# V1_6.net
KiCad netlist of a schematic drawn in Altium Designer
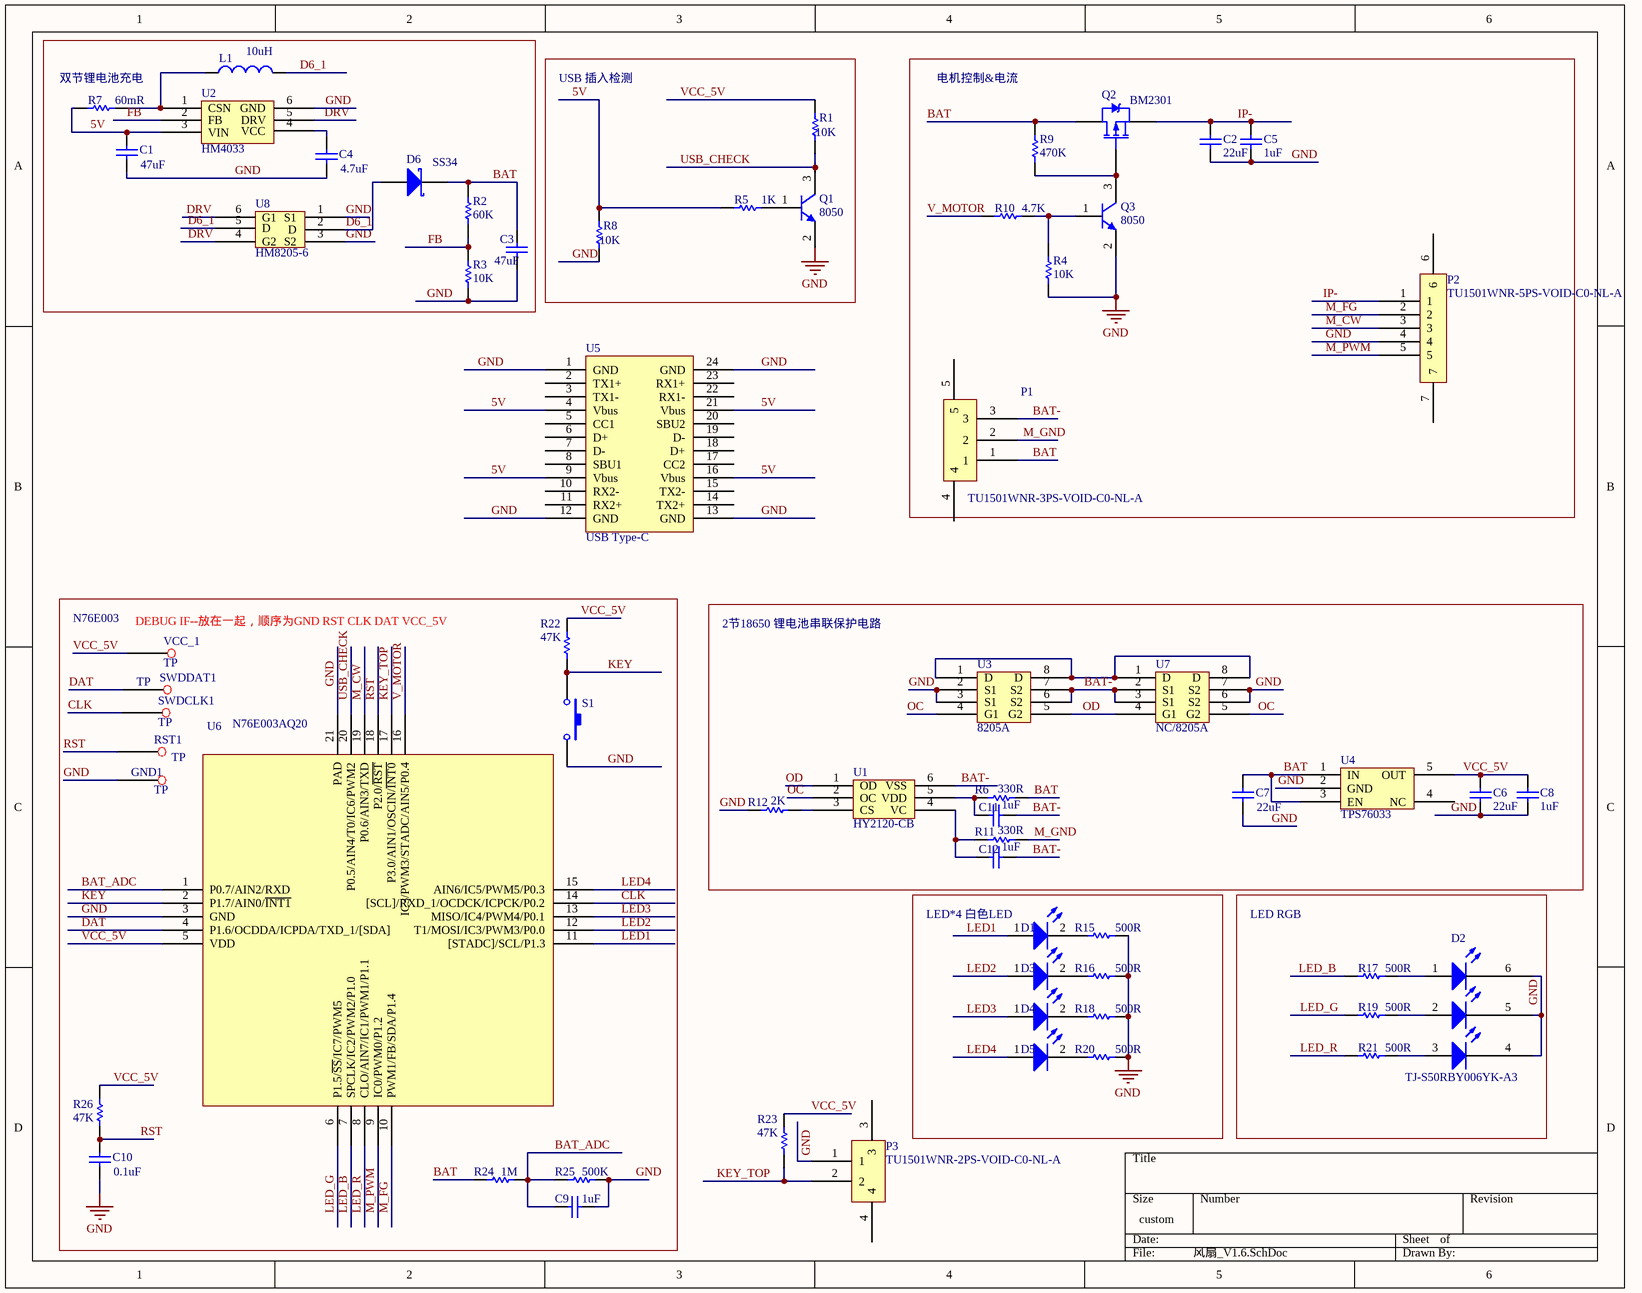
[diagram p0: 风扇_V1.6.SchDoc]

(export (version "E")
  (design (tool "Eeschema 10.0.6"))
  (components
    (comp (ref "C1")
      (value "47uF")
      (footprint "C-0603")
      (description "Capacitor")
      (fields (field (name "PUBLISHER") "Altium Limited"))
      (libsource (lib "Miscellaneous Devices") (part "Cap"))
    )
    (comp (ref "C2")
      (value "22uF")
      (footprint "C-0603")
      (description "Capacitor")
      (fields (field (name "PUBLISHER") "Altium Limited"))
      (libsource (lib "Miscellaneous Devices") (part "Cap"))
    )
    (comp (ref "C3")
      (value "47uF")
      (footprint "C-0603")
      (description "Capacitor")
      (fields (field (name "PUBLISHER") "Altium Limited"))
      (libsource (lib "Miscellaneous Devices") (part "Cap"))
    )
    (comp (ref "C4")
      (value "4.7uF")
      (footprint "C-0402")
      (description "Capacitor")
      (fields (field (name "PUBLISHER") "Altium Limited"))
      (libsource (lib "Miscellaneous Devices") (part "Cap"))
    )
    (comp (ref "C5")
      (value "1uF")
      (footprint "C-0402")
      (description "Capacitor")
      (fields (field (name "PUBLISHER") "Altium Limited"))
      (libsource (lib "Miscellaneous Devices") (part "Cap"))
    )
    (comp (ref "C6")
      (value "22uF")
      (footprint "C-0603")
      (description "Capacitor")
      (fields (field (name "PUBLISHER") "Altium Limited"))
      (libsource (lib "Miscellaneous Devices") (part "Cap"))
    )
    (comp (ref "C7")
      (value "22uF")
      (footprint "C-0603")
      (description "Capacitor")
      (fields (field (name "PUBLISHER") "Altium Limited"))
      (libsource (lib "Miscellaneous Devices") (part "Cap"))
    )
    (comp (ref "C8")
      (value "1uF")
      (footprint "C-0402")
      (description "Capacitor")
      (fields (field (name "PUBLISHER") "Altium Limited"))
      (libsource (lib "Miscellaneous Devices") (part "Cap"))
    )
    (comp (ref "C9")
      (value "1uF")
      (footprint "C-0402")
      (description "Capacitor")
      (fields (field (name "PUBLISHER") "Altium Limited"))
      (libsource (lib "Miscellaneous Devices") (part "Cap"))
    )
    (comp (ref "C10")
      (value "0.1uF")
      (footprint "C-0402")
      (description "Capacitor")
      (fields (field (name "PUBLISHER") "Altium Limited"))
      (libsource (lib "Miscellaneous Devices") (part "Cap"))
    )
    (comp (ref "C11")
      (value "1uF")
      (footprint "C-0402")
      (description "Capacitor")
      (fields (field (name "PUBLISHER") "Altium Limited"))
      (libsource (lib "Miscellaneous Devices") (part "Cap"))
    )
    (comp (ref "C12")
      (value "1uF")
      (footprint "C-0402")
      (description "Capacitor")
      (fields (field (name "PUBLISHER") "Altium Limited"))
      (libsource (lib "Miscellaneous Devices") (part "Cap"))
    )
    (comp (ref "D1")
      (value "LED0")
      (footprint "LED-0603")
      (description "Typical INFRARED GaAs LED")
      (fields (field (name "PUBLISHER") "Altium Limited"))
      (libsource (lib "Miscellaneous Devices") (part "LED0"))
    )
    (comp (ref "D2")
      (value "TJ-S50RBY006YK-A3")
      (footprint "TJ-S50RBY006YK-A3")
      (libsource (lib "Others_IC_SCH_LIB") (part "TJ-S50RBY006YK-A3"))
    )
    (comp (ref "D3")
      (value "LED0")
      (footprint "LED-0603")
      (description "Typical INFRARED GaAs LED")
      (fields (field (name "PUBLISHER") "Altium Limited"))
      (libsource (lib "Miscellaneous Devices") (part "LED0"))
    )
    (comp (ref "D4")
      (value "LED0")
      (footprint "LED-0603")
      (description "Typical INFRARED GaAs LED")
      (fields (field (name "PUBLISHER") "Altium Limited"))
      (libsource (lib "Miscellaneous Devices") (part "LED0"))
    )
    (comp (ref "D5")
      (value "LED0")
      (footprint "LED-0603")
      (description "Typical INFRARED GaAs LED")
      (fields (field (name "PUBLISHER") "Altium Limited"))
      (libsource (lib "Miscellaneous Devices") (part "LED0"))
    )
    (comp (ref "D6")
      (value "SS34")
      (footprint "HM4033 V1.0:DSMD")
      (description "Schottky Rectifier")
      (fields (field (name "PUBLISHER") "Altium Limited"))
      (libsource (lib "Miscellaneous Devices") (part "Diode 10TQ035"))
    )
    (comp (ref "GND1") (value "TP") (footprint "TP-1.5") (libsource (lib "Others_IC_SCH_LIB") (part "TP")))
    (comp (ref "L1")
      (value "10uH")
      (footprint "L-SMD")
      (description "Inductor")
      (fields (field (name "PUBLISHER") "Altium Limited"))
      (libsource (lib "Miscellaneous Devices") (part "Inductor"))
    )
    (comp (ref "P1")
      (value "TU1501WNR-3PS-VOID-C0-NL-A")
      (footprint "TU1501WNR-3PS-VOID-*-NL-A")
      (libsource (lib "Others_IC_SCH_LIB") (part "TU1501WNR-3PS-VOID-C0-NL-A"))
    )
    (comp (ref "P2")
      (value "TU1501WNR-5PS-VOID-C0-NL-A")
      (footprint "TU1501WNR-5PS-VOID-*-NL-A")
      (libsource (lib "Others_IC_SCH_LIB") (part "TU1501WNR-5PS-VOID-C0-NL-A"))
    )
    (comp (ref "P3")
      (value "TU1501WNR-2PS-VOID-C0-NL-A")
      (footprint "TU1501WNR-2PS-VOID-*-NL-A")
      (libsource (lib "Others_IC_SCH_LIB") (part "TU1501WNR-2PS-VOID-C0-NL-A"))
    )
    (comp (ref "Q1")
      (value "8050")
      (footprint "SOT-23")
      (description "NPN Bipolar Transistor")
      (fields (field (name "PUBLISHER") "Altium Limited"))
      (libsource (lib "Miscellaneous Devices") (part "NPN"))
    )
    (comp (ref "Q2")
      (value "BM2301")
      (footprint "SOT-23")
      (description "P-Channel Power MOSFET")
      (fields (field (name "PUBLISHER") "Altium Limited"))
      (libsource (lib "Miscellaneous Devices") (part "PMOS-2"))
    )
    (comp (ref "Q3")
      (value "8050")
      (footprint "SOT-23")
      (description "NPN Bipolar Transistor")
      (fields (field (name "PUBLISHER") "Altium Limited"))
      (libsource (lib "Miscellaneous Devices") (part "NPN"))
    )
    (comp (ref "R1")
      (value "10K")
      (footprint "R-0402")
      (description "Resistor")
      (fields (field (name "PUBLISHER") "Altium Limited"))
      (libsource (lib "Miscellaneous Devices") (part "Res1"))
    )
    (comp (ref "R2")
      (value "60K")
      (footprint "R-0402")
      (description "Resistor")
      (fields (field (name "PUBLISHER") "Altium Limited"))
      (libsource (lib "Miscellaneous Devices") (part "Res1"))
    )
    (comp (ref "R3")
      (value "10K")
      (footprint "R-0402")
      (description "Resistor")
      (fields (field (name "PUBLISHER") "Altium Limited"))
      (libsource (lib "Miscellaneous Devices") (part "Res1"))
    )
    (comp (ref "R4")
      (value "10K")
      (footprint "R-0402")
      (description "Resistor")
      (fields (field (name "PUBLISHER") "Altium Limited"))
      (libsource (lib "Miscellaneous Devices") (part "Res1"))
    )
    (comp (ref "R5")
      (value "1K")
      (footprint "R-0402")
      (description "Resistor")
      (fields (field (name "PUBLISHER") "Altium Limited"))
      (libsource (lib "Miscellaneous Devices") (part "Res1"))
    )
    (comp (ref "R6")
      (value "330R")
      (footprint "R-0402")
      (description "Resistor")
      (fields (field (name "PUBLISHER") "Altium Limited"))
      (libsource (lib "Miscellaneous Devices") (part "Res1"))
    )
    (comp (ref "R7")
      (value "60mR")
      (footprint "R-0402")
      (description "Resistor")
      (fields (field (name "PUBLISHER") "Altium Limited"))
      (libsource (lib "Miscellaneous Devices") (part "Res1"))
    )
    (comp (ref "R8")
      (value "10K")
      (footprint "R-0402")
      (description "Resistor")
      (fields (field (name "PUBLISHER") "Altium Limited"))
      (libsource (lib "Miscellaneous Devices") (part "Res1"))
    )
    (comp (ref "R9")
      (value "470K")
      (footprint "R-0402")
      (description "Resistor")
      (fields (field (name "PUBLISHER") "Altium Limited"))
      (libsource (lib "Miscellaneous Devices") (part "Res1"))
    )
    (comp (ref "R10")
      (value "4.7K")
      (footprint "R-0402")
      (description "Resistor")
      (fields (field (name "PUBLISHER") "Altium Limited"))
      (libsource (lib "Miscellaneous Devices") (part "Res1"))
    )
    (comp (ref "R11")
      (value "330R")
      (footprint "R-0402")
      (description "Resistor")
      (fields (field (name "PUBLISHER") "Altium Limited"))
      (libsource (lib "Miscellaneous Devices") (part "Res1"))
    )
    (comp (ref "R12")
      (value "2K")
      (footprint "R-0402")
      (description "Resistor")
      (fields (field (name "PUBLISHER") "Altium Limited"))
      (libsource (lib "Miscellaneous Devices") (part "Res1"))
    )
    (comp (ref "R15")
      (value "500R")
      (footprint "R-0402")
      (description "Resistor")
      (fields (field (name "PUBLISHER") "Altium Limited"))
      (libsource (lib "Miscellaneous Devices") (part "Res1"))
    )
    (comp (ref "R16")
      (value "500R")
      (footprint "R-0402")
      (description "Resistor")
      (fields (field (name "PUBLISHER") "Altium Limited"))
      (libsource (lib "Miscellaneous Devices") (part "Res1"))
    )
    (comp (ref "R17")
      (value "500R")
      (footprint "R-0402")
      (description "Resistor")
      (fields (field (name "PUBLISHER") "Altium Limited"))
      (libsource (lib "Miscellaneous Devices") (part "Res1"))
    )
    (comp (ref "R18")
      (value "500R")
      (footprint "R-0402")
      (description "Resistor")
      (fields (field (name "PUBLISHER") "Altium Limited"))
      (libsource (lib "Miscellaneous Devices") (part "Res1"))
    )
    (comp (ref "R19")
      (value "500R")
      (footprint "R-0402")
      (description "Resistor")
      (fields (field (name "PUBLISHER") "Altium Limited"))
      (libsource (lib "Miscellaneous Devices") (part "Res1"))
    )
    (comp (ref "R20")
      (value "500R")
      (footprint "R-0402")
      (description "Resistor")
      (fields (field (name "PUBLISHER") "Altium Limited"))
      (libsource (lib "Miscellaneous Devices") (part "Res1"))
    )
    (comp (ref "R21")
      (value "500R")
      (footprint "R-0402")
      (description "Resistor")
      (fields (field (name "PUBLISHER") "Altium Limited"))
      (libsource (lib "Miscellaneous Devices") (part "Res1"))
    )
    (comp (ref "R22")
      (value "47K")
      (footprint "R-0402")
      (description "Resistor")
      (fields (field (name "PUBLISHER") "Altium Limited"))
      (libsource (lib "Miscellaneous Devices") (part "Res1"))
    )
    (comp (ref "R23")
      (value "47K")
      (footprint "R-0402")
      (description "Resistor")
      (fields (field (name "PUBLISHER") "Altium Limited"))
      (libsource (lib "Miscellaneous Devices") (part "Res1"))
    )
    (comp (ref "R24")
      (value "1M")
      (footprint "R-0402")
      (description "Resistor")
      (fields (field (name "PUBLISHER") "Altium Limited"))
      (libsource (lib "Miscellaneous Devices") (part "Res1"))
    )
    (comp (ref "R25")
      (value "500K")
      (footprint "R-0402")
      (description "Resistor")
      (fields (field (name "PUBLISHER") "Altium Limited"))
      (libsource (lib "Miscellaneous Devices") (part "Res1"))
    )
    (comp (ref "R26")
      (value "47K")
      (footprint "R-0402")
      (description "Resistor")
      (fields (field (name "PUBLISHER") "Altium Limited"))
      (libsource (lib "Miscellaneous Devices") (part "Res1"))
    )
    (comp (ref "RST1") (value "TP") (footprint "TP-1.5") (libsource (lib "Others_IC_SCH_LIB") (part "TP")))
    (comp (ref "S1")
      (value "SW-PB")
      (footprint "SWITCH-4P-SMT")
      (description "Switch")
      (fields (field (name "PUBLISHER") "Altium Limited"))
      (libsource (lib "Miscellaneous Devices") (part "SW-PB"))
    )
    (comp (ref "SWDCLK1") (value "TP") (footprint "TP-1.5") (libsource (lib "Others_IC_SCH_LIB") (part "TP")))
    (comp (ref "SWDDAT1") (value "TP") (footprint "TP-1.5") (libsource (lib "Others_IC_SCH_LIB") (part "TP")))
    (comp (ref "U1")
      (value "HY2120-CB")
      (footprint "SOT-23-6L")
      (libsource (lib "Others_IC_SCH_LIB") (part "HY2120"))
    )
    (comp (ref "U2")
      (value "HM4033")
      (footprint "SOT-23-6L")
      (libsource (lib "Others_IC_SCH_LIB") (part "HM4033"))
    )
    (comp (ref "U3")
      (value "8205A")
      (footprint "TSSOP8")
      (libsource (lib "Others_IC_SCH_LIB") (part "8205A"))
    )
    (comp (ref "U4")
      (value "TPS76033")
      (footprint "SOT-23-5")
      (libsource (lib "Others_IC_SCH_LIB") (part "TPS76033"))
    )
    (comp (ref "U5")
      (value "USB Type-C")
      (footprint "USB-type C")
      (libsource (lib "Others_IC_SCH_LIB") (part "USB Type-C"))
    )
    (comp (ref "U6")
      (value "N76E003AQ20")
      (footprint "QFN-20 0.4mm")
      (libsource (lib "Others_IC_SCH_LIB") (part "N76E003AQ20"))
    )
    (comp (ref "U7")
      (value "NC/8205A")
      (footprint "TSSOP8")
      (libsource (lib "Others_IC_SCH_LIB") (part "8205A"))
    )
    (comp (ref "U8")
      (value "HM8205-6")
      (footprint "SOT-23-6L")
      (libsource (lib "Others_IC_SCH_LIB") (part "HM8205-6"))
    )
    (comp (ref "VCC_1") (value "TP") (footprint "TP-1.5") (libsource (lib "Others_IC_SCH_LIB") (part "TP")))
  )
  (nets
    (net (code "1") (name "/5V") (class "Default")
      (node (ref "C1") (pin "1") (pinfunction "1_1") (pintype "passive"))
      (node (ref "R5") (pin "1") (pinfunction "1_1") (pintype "passive"))
      (node (ref "R7") (pin "2") (pinfunction "2_2") (pintype "passive"))
      (node (ref "R8") (pin "1") (pinfunction "1_1") (pintype "passive"))
      (node (ref "U2") (pin "3") (pinfunction "VIN_3") (pintype "passive"))
      (node (ref "U5") (pin "16") (pinfunction "Vbus_16") (pintype "passive"))
      (node (ref "U5") (pin "21") (pinfunction "Vbus_21") (pintype "passive"))
      (node (ref "U5") (pin "4") (pinfunction "Vbus_4") (pintype "passive"))
      (node (ref "U5") (pin "9") (pinfunction "Vbus_9") (pintype "passive"))
    )
    (net (code "2") (name "/BAT") (class "Default")
      (node (ref "C3") (pin "2") (pinfunction "2_2") (pintype "passive"))
      (node (ref "C7") (pin "2") (pinfunction "2_2") (pintype "passive"))
      (node (ref "D6") (pin "1") (pinfunction "K_1") (pintype "passive"))
      (node (ref "P1") (pin "1") (pinfunction "1_1") (pintype "passive"))
      (node (ref "Q2") (pin "2") (pinfunction "D_2") (pintype "passive"))
      (node (ref "R2") (pin "1") (pinfunction "1_1") (pintype "passive"))
      (node (ref "R24") (pin "1") (pinfunction "1_1") (pintype "passive"))
      (node (ref "R6") (pin "2") (pinfunction "2_2") (pintype "passive"))
      (node (ref "R9") (pin "2") (pinfunction "2_2") (pintype "passive"))
      (node (ref "U4") (pin "1") (pinfunction "IN_1") (pintype "passive"))
      (node (ref "U4") (pin "3") (pinfunction "EN_3") (pintype "passive"))
    )
    (net (code "3") (name "/BAT-") (class "Default")
      (node (ref "C11") (pin "1") (pinfunction "1_1") (pintype "passive"))
      (node (ref "C12") (pin "1") (pinfunction "1_1") (pintype "passive"))
      (node (ref "P1") (pin "3") (pinfunction "3_3") (pintype "passive"))
      (node (ref "U1") (pin "6") (pinfunction "VSS_6") (pintype "passive"))
      (node (ref "U3") (pin "6") (pinfunction "S2_6") (pintype "passive"))
      (node (ref "U3") (pin "7") (pinfunction "S2_7") (pintype "passive"))
      (node (ref "U7") (pin "2") (pinfunction "S1_2") (pintype "passive"))
      (node (ref "U7") (pin "3") (pinfunction "S1_3") (pintype "passive"))
    )
    (net (code "4") (name "/BAT_ADC") (class "Default")
      (node (ref "C9") (pin "2") (pinfunction "2_2") (pintype "passive"))
      (node (ref "R24") (pin "2") (pinfunction "2_2") (pintype "passive"))
      (node (ref "R25") (pin "1") (pinfunction "1_1") (pintype "passive"))
      (node (ref "U6") (pin "1") (pinfunction "P0.7/AIN2/RXD_1") (pintype "passive"))
    )
    (net (code "5") (name "/CLK") (class "Default")
      (node (ref "SWDCLK1") (pin "1") (pinfunction "1_1") (pintype "passive"))
      (node (ref "U6") (pin "14") (pinfunction "[SCL]/RXD_1/OCDCK/ICPCK/P0.2_14") (pintype "passive"))
    )
    (net (code "6") (name "/D6_1") (class "Default")
      (node (ref "D6") (pin "3") (pinfunction "A_3") (pintype "passive"))
      (node (ref "L1") (pin "2") (pinfunction "2_2") (pintype "passive"))
      (node (ref "U8") (pin "2") (pinfunction "D_2") (pintype "passive"))
      (node (ref "U8") (pin "5") (pinfunction "D_5") (pintype "passive"))
    )
    (net (code "7") (name "/DAT") (class "Default")
      (node (ref "SWDDAT1") (pin "1") (pinfunction "1_1") (pintype "passive"))
      (node (ref "U6") (pin "4") (pinfunction "P1.6/OCDDA/ICPDA/TXD_1/[SDA]_4") (pintype "passive"))
    )
    (net (code "8") (name "/DRV") (class "Default")
      (node (ref "U2") (pin "5") (pinfunction "DRV_5") (pintype "passive"))
      (node (ref "U8") (pin "4") (pinfunction "G2_4") (pintype "passive"))
      (node (ref "U8") (pin "6") (pinfunction "G1_6") (pintype "passive"))
    )
    (net (code "9") (name "/FB") (class "Default")
      (node (ref "R2") (pin "2") (pinfunction "2_2") (pintype "passive"))
      (node (ref "R3") (pin "1") (pinfunction "1_1") (pintype "passive"))
      (node (ref "U2") (pin "2") (pinfunction "FB_2") (pintype "passive"))
    )
    (net (code "10") (name "/IP-") (class "Default")
      (node (ref "C2") (pin "2") (pinfunction "2_2") (pintype "passive"))
      (node (ref "C5") (pin "2") (pinfunction "2_2") (pintype "passive"))
      (node (ref "P2") (pin "1") (pinfunction "1_1") (pintype "passive"))
      (node (ref "Q2") (pin "3") (pinfunction "S_3") (pintype "passive"))
    )
    (net (code "11") (name "/KEY") (class "Default")
      (node (ref "R22") (pin "1") (pinfunction "1_1") (pintype "passive"))
      (node (ref "S1") (pin "1") (pinfunction "1_1") (pintype "passive"))
      (node (ref "U6") (pin "2") (pinfunction "P1.7/AIN0/~{INT1}_2") (pintype "passive"))
    )
    (net (code "12") (name "/KEY_TOP") (class "Default")
      (node (ref "P3") (pin "2") (pinfunction "2_2") (pintype "passive"))
      (node (ref "R23") (pin "1") (pinfunction "1_1") (pintype "passive"))
      (node (ref "U6") (pin "17") (pinfunction "P3.0/AIN1/OSCIN/~{INT0}_17") (pintype "passive"))
    )
    (net (code "13") (name "/LED1") (class "Default")
      (node (ref "D1") (pin "1") (pinfunction "A_1") (pintype "passive"))
      (node (ref "U6") (pin "11") (pinfunction "[STADC]/SCL/P1.3_11") (pintype "passive"))
    )
    (net (code "14") (name "/LED2") (class "Default")
      (node (ref "D3") (pin "1") (pinfunction "A_1") (pintype "passive"))
      (node (ref "U6") (pin "12") (pinfunction "T1/MOSI/IC3/PWM3/P0.0_12") (pintype "passive"))
    )
    (net (code "15") (name "/LED3") (class "Default")
      (node (ref "D4") (pin "1") (pinfunction "A_1") (pintype "passive"))
      (node (ref "U6") (pin "13") (pinfunction "MISO/IC4/PWM4/P0.1_13") (pintype "passive"))
    )
    (net (code "16") (name "/LED4") (class "Default")
      (node (ref "D5") (pin "1") (pinfunction "A_1") (pintype "passive"))
      (node (ref "U6") (pin "15") (pinfunction "AIN6/IC5/PWM5/P0.3_15") (pintype "passive"))
    )
    (net (code "17") (name "/LED_B") (class "Default")
      (node (ref "R17") (pin "1") (pinfunction "1_1") (pintype "passive"))
      (node (ref "U6") (pin "7") (pinfunction "SPCLK/IC2/PWM2/P1.0_7") (pintype "passive"))
    )
    (net (code "18") (name "/LED_G") (class "Default")
      (node (ref "R19") (pin "1") (pinfunction "1_1") (pintype "passive"))
      (node (ref "U6") (pin "6") (pinfunction "P1.5/~{SS}/IC7/PWM5_6") (pintype "passive"))
    )
    (net (code "19") (name "/LED_R") (class "Default")
      (node (ref "R21") (pin "1") (pinfunction "1_1") (pintype "passive"))
      (node (ref "U6") (pin "8") (pinfunction "CLO/AIN7/IC1/PWM1/P1.1_8") (pintype "passive"))
    )
    (net (code "20") (name "/M_CW") (class "Default")
      (node (ref "P2") (pin "3") (pinfunction "3_3") (pintype "passive"))
      (node (ref "U6") (pin "19") (pinfunction "P0.6/AIN3/TXD_19") (pintype "passive"))
    )
    (net (code "21") (name "/M_FG") (class "Default")
      (node (ref "P2") (pin "2") (pinfunction "2_2") (pintype "passive"))
      (node (ref "U6") (pin "10") (pinfunction "PWM1/FB/SDA/P1.4_10") (pintype "passive"))
    )
    (net (code "22") (name "/M_GND") (class "Default")
      (node (ref "P1") (pin "2") (pinfunction "2_2") (pintype "passive"))
      (node (ref "R11") (pin "2") (pinfunction "2_2") (pintype "passive"))
    )
    (net (code "23") (name "/M_PWM") (class "Default")
      (node (ref "P2") (pin "5") (pinfunction "5_5") (pintype "passive"))
      (node (ref "U6") (pin "9") (pinfunction "IC0/PWM0/P1.2_9") (pintype "passive"))
    )
    (net (code "24") (name "/OC") (class "Default")
      (node (ref "U1") (pin "2") (pinfunction "OC_2") (pintype "passive"))
      (node (ref "U3") (pin "4") (pinfunction "G1_4") (pintype "passive"))
      (node (ref "U7") (pin "5") (pinfunction "G2_5") (pintype "passive"))
    )
    (net (code "25") (name "/OD") (class "Default")
      (node (ref "U1") (pin "1") (pinfunction "OD_1") (pintype "passive"))
      (node (ref "U3") (pin "5") (pinfunction "G2_5") (pintype "passive"))
      (node (ref "U7") (pin "4") (pinfunction "G1_4") (pintype "passive"))
    )
    (net (code "26") (name "/RST") (class "Default")
      (node (ref "C10") (pin "2") (pinfunction "2_2") (pintype "passive"))
      (node (ref "R26") (pin "1") (pinfunction "1_1") (pintype "passive"))
      (node (ref "RST1") (pin "1") (pinfunction "1_1") (pintype "passive"))
      (node (ref "U6") (pin "18") (pinfunction "P2.0/~{RST}_18") (pintype "passive"))
    )
    (net (code "27") (name "/USB_CHECK") (class "Default")
      (node (ref "Q1") (pin "3") (pinfunction "C_3") (pintype "passive"))
      (node (ref "R1") (pin "1") (pinfunction "1_1") (pintype "passive"))
      (node (ref "U6") (pin "20") (pinfunction "P0.5/AIN4/T0/IC6/PWM2_20") (pintype "passive"))
    )
    (net (code "28") (name "/VCC_5V") (class "Default")
      (node (ref "C6") (pin "2") (pinfunction "2_2") (pintype "passive"))
      (node (ref "C8") (pin "2") (pinfunction "2_2") (pintype "passive"))
      (node (ref "R1") (pin "2") (pinfunction "2_2") (pintype "passive"))
      (node (ref "R22") (pin "2") (pinfunction "2_2") (pintype "passive"))
      (node (ref "R23") (pin "2") (pinfunction "2_2") (pintype "passive"))
      (node (ref "R26") (pin "2") (pinfunction "2_2") (pintype "passive"))
      (node (ref "U4") (pin "5") (pinfunction "OUT_5") (pintype "passive"))
      (node (ref "U6") (pin "5") (pinfunction "VDD_5") (pintype "passive"))
      (node (ref "VCC_1") (pin "1") (pinfunction "1_1") (pintype "passive"))
    )
    (net (code "29") (name "/V_MOTOR") (class "Default")
      (node (ref "R10") (pin "1") (pinfunction "1_1") (pintype "passive"))
      (node (ref "U6") (pin "16") (pinfunction "IC3/PWM3/STADC/AIN5/P0.4_16") (pintype "passive"))
    )
    (net (code "30") (name "GND") (class "Default")
      (node (ref "C1") (pin "2") (pinfunction "2_2") (pintype "passive"))
      (node (ref "C10") (pin "1") (pinfunction "1_1") (pintype "passive"))
      (node (ref "C2") (pin "1") (pinfunction "1_1") (pintype "passive"))
      (node (ref "C3") (pin "1") (pinfunction "1_1") (pintype "passive"))
      (node (ref "C4") (pin "2") (pinfunction "2_2") (pintype "passive"))
      (node (ref "C5") (pin "1") (pinfunction "1_1") (pintype "passive"))
      (node (ref "C6") (pin "1") (pinfunction "1_1") (pintype "passive"))
      (node (ref "C7") (pin "1") (pinfunction "1_1") (pintype "passive"))
      (node (ref "C8") (pin "1") (pinfunction "1_1") (pintype "passive"))
      (node (ref "C9") (pin "1") (pinfunction "1_1") (pintype "passive"))
      (node (ref "D2") (pin "4") (pinfunction "4_4") (pintype "passive"))
      (node (ref "D2") (pin "5") (pinfunction "5_5") (pintype "passive"))
      (node (ref "D2") (pin "6") (pinfunction "6_6") (pintype "passive"))
      (node (ref "GND1") (pin "1") (pinfunction "1_1") (pintype "passive"))
      (node (ref "P2") (pin "4") (pinfunction "4_4") (pintype "passive"))
      (node (ref "P3") (pin "1") (pinfunction "1_1") (pintype "passive"))
      (node (ref "Q1") (pin "2") (pinfunction "E_2") (pintype "passive"))
      (node (ref "Q3") (pin "2") (pinfunction "E_2") (pintype "passive"))
      (node (ref "R12") (pin "1") (pinfunction "1_1") (pintype "passive"))
      (node (ref "R15") (pin "2") (pinfunction "2_2") (pintype "passive"))
      (node (ref "R16") (pin "2") (pinfunction "2_2") (pintype "passive"))
      (node (ref "R18") (pin "2") (pinfunction "2_2") (pintype "passive"))
      (node (ref "R20") (pin "2") (pinfunction "2_2") (pintype "passive"))
      (node (ref "R25") (pin "2") (pinfunction "2_2") (pintype "passive"))
      (node (ref "R3") (pin "2") (pinfunction "2_2") (pintype "passive"))
      (node (ref "R4") (pin "1") (pinfunction "1_1") (pintype "passive"))
      (node (ref "R8") (pin "2") (pinfunction "2_2") (pintype "passive"))
      (node (ref "S1") (pin "2") (pinfunction "2_2") (pintype "passive"))
      (node (ref "U2") (pin "6") (pinfunction "GND_6") (pintype "passive"))
      (node (ref "U3") (pin "2") (pinfunction "S1_2") (pintype "passive"))
      (node (ref "U3") (pin "3") (pinfunction "S1_3") (pintype "passive"))
      (node (ref "U4") (pin "2") (pinfunction "GND_2") (pintype "passive"))
      (node (ref "U5") (pin "1") (pinfunction "GND_1") (pintype "passive"))
      (node (ref "U5") (pin "12") (pinfunction "GND_12") (pintype "passive"))
      (node (ref "U5") (pin "13") (pinfunction "GND_13") (pintype "passive"))
      (node (ref "U5") (pin "24") (pinfunction "GND_24") (pintype "passive"))
      (node (ref "U6") (pin "21") (pinfunction "PAD_21") (pintype "passive"))
      (node (ref "U6") (pin "3") (pinfunction "GND_3") (pintype "passive"))
      (node (ref "U7") (pin "6") (pinfunction "S2_6") (pintype "passive"))
      (node (ref "U7") (pin "7") (pinfunction "S2_7") (pintype "passive"))
      (node (ref "U8") (pin "1") (pinfunction "S1_1") (pintype "passive"))
      (node (ref "U8") (pin "3") (pinfunction "S2_3") (pintype "passive"))
    )
    (net (code "31") (name "Net-(D1-K)") (class "Default")
      (node (ref "D1") (pin "2") (pinfunction "K_2") (pintype "passive"))
      (node (ref "R15") (pin "1") (pinfunction "1_1") (pintype "passive"))
    )
    (net (code "32") (name "Net-(D2-Pad1)") (class "Default")
      (node (ref "D2") (pin "1") (pinfunction "1_1") (pintype "passive"))
      (node (ref "R17") (pin "2") (pinfunction "2_2") (pintype "passive"))
    )
    (net (code "33") (name "Net-(D2-Pad2)") (class "Default")
      (node (ref "D2") (pin "2") (pinfunction "2_2") (pintype "passive"))
      (node (ref "R19") (pin "2") (pinfunction "2_2") (pintype "passive"))
    )
    (net (code "34") (name "Net-(D2-Pad3)") (class "Default")
      (node (ref "D2") (pin "3") (pinfunction "3_3") (pintype "passive"))
      (node (ref "R21") (pin "2") (pinfunction "2_2") (pintype "passive"))
    )
    (net (code "35") (name "Net-(D3-K)") (class "Default")
      (node (ref "D3") (pin "2") (pinfunction "K_2") (pintype "passive"))
      (node (ref "R16") (pin "1") (pinfunction "1_1") (pintype "passive"))
    )
    (net (code "36") (name "Net-(D4-K)") (class "Default")
      (node (ref "D4") (pin "2") (pinfunction "K_2") (pintype "passive"))
      (node (ref "R18") (pin "1") (pinfunction "1_1") (pintype "passive"))
    )
    (net (code "37") (name "Net-(D5-K)") (class "Default")
      (node (ref "D5") (pin "2") (pinfunction "K_2") (pintype "passive"))
      (node (ref "R20") (pin "1") (pinfunction "1_1") (pintype "passive"))
    )
    (net (code "38") (name "Net-(Q1-B)") (class "Default")
      (node (ref "Q1") (pin "1") (pinfunction "B_1") (pintype "passive"))
      (node (ref "R5") (pin "2") (pinfunction "2_2") (pintype "passive"))
    )
    (net (code "39") (name "Net-(Q2-G)") (class "Default")
      (node (ref "Q2") (pin "1") (pinfunction "G_1") (pintype "passive"))
      (node (ref "Q3") (pin "3") (pinfunction "C_3") (pintype "passive"))
      (node (ref "R9") (pin "1") (pinfunction "1_1") (pintype "passive"))
    )
    (net (code "40") (name "Net-(Q3-B)") (class "Default")
      (node (ref "Q3") (pin "1") (pinfunction "B_1") (pintype "passive"))
      (node (ref "R10") (pin "2") (pinfunction "2_2") (pintype "passive"))
      (node (ref "R4") (pin "2") (pinfunction "2_2") (pintype "passive"))
    )
    (net (code "41") (name "Net-(U1-CS)") (class "Default")
      (node (ref "R12") (pin "2") (pinfunction "2_2") (pintype "passive"))
      (node (ref "U1") (pin "3") (pinfunction "CS_3") (pintype "passive"))
    )
    (net (code "42") (name "Net-(U1-VC)") (class "Default")
      (node (ref "C12") (pin "2") (pinfunction "2_2") (pintype "passive"))
      (node (ref "R11") (pin "1") (pinfunction "1_1") (pintype "passive"))
      (node (ref "U1") (pin "4") (pinfunction "VC_4") (pintype "passive"))
    )
    (net (code "43") (name "Net-(U1-VDD)") (class "Default")
      (node (ref "C11") (pin "2") (pinfunction "2_2") (pintype "passive"))
      (node (ref "R6") (pin "1") (pinfunction "1_1") (pintype "passive"))
      (node (ref "U1") (pin "5") (pinfunction "VDD_5") (pintype "passive"))
    )
    (net (code "44") (name "Net-(U2-CSN)") (class "Default")
      (node (ref "L1") (pin "1") (pinfunction "1_1") (pintype "passive"))
      (node (ref "R7") (pin "1") (pinfunction "1_1") (pintype "passive"))
      (node (ref "U2") (pin "1") (pinfunction "CSN_1") (pintype "passive"))
    )
    (net (code "45") (name "Net-(U2-VCC)") (class "Default")
      (node (ref "C4") (pin "1") (pinfunction "1_1") (pintype "passive"))
      (node (ref "U2") (pin "4") (pinfunction "VCC_4") (pintype "passive"))
    )
    (net (code "46") (name "Net-(U3-D-Pad1)") (class "Default")
      (node (ref "U3") (pin "1") (pinfunction "D_1") (pintype "passive"))
      (node (ref "U3") (pin "8") (pinfunction "D_8") (pintype "passive"))
      (node (ref "U7") (pin "1") (pinfunction "D_1") (pintype "passive"))
      (node (ref "U7") (pin "8") (pinfunction "D_8") (pintype "passive"))
    )
    (net (code "47") (name "unconnected-(P1-Pad4)") (class "Default")
      (node (ref "P1") (pin "4") (pinfunction "4_4") (pintype "passive"))
    )
    (net (code "48") (name "unconnected-(P1-Pad5)") (class "Default")
      (node (ref "P1") (pin "5") (pinfunction "5_5") (pintype "passive"))
    )
    (net (code "49") (name "unconnected-(P2-Pad6)") (class "Default")
      (node (ref "P2") (pin "6") (pinfunction "6_6") (pintype "passive"))
    )
    (net (code "50") (name "unconnected-(P2-Pad7)") (class "Default")
      (node (ref "P2") (pin "7") (pinfunction "7_7") (pintype "passive"))
    )
    (net (code "51") (name "unconnected-(P3-Pad3)") (class "Default")
      (node (ref "P3") (pin "3") (pinfunction "3_3") (pintype "passive"))
    )
    (net (code "52") (name "unconnected-(P3-Pad4)") (class "Default")
      (node (ref "P3") (pin "4") (pinfunction "4_4") (pintype "passive"))
    )
    (net (code "53") (name "unconnected-(U4-NC-Pad4)") (class "Default")
      (node (ref "U4") (pin "4") (pinfunction "NC_4") (pintype "passive"))
    )
    (net (code "54") (name "unconnected-(U5-CC1-Pad5)") (class "Default")
      (node (ref "U5") (pin "5") (pinfunction "CC1_5") (pintype "passive"))
    )
    (net (code "55") (name "unconnected-(U5-CC2-Pad17)") (class "Default")
      (node (ref "U5") (pin "17") (pinfunction "CC2_17") (pintype "passive"))
    )
    (net (code "56") (name "unconnected-(U5-D+-Pad6)") (class "Default")
      (node (ref "U5") (pin "6") (pinfunction "D+_6") (pintype "passive"))
    )
    (net (code "57") (name "unconnected-(U5-D+-Pad18)") (class "Default")
      (node (ref "U5") (pin "18") (pinfunction "D+_18") (pintype "passive"))
    )
    (net (code "58") (name "unconnected-(U5-D--Pad7)") (class "Default")
      (node (ref "U5") (pin "7") (pinfunction "D-_7") (pintype "passive"))
    )
    (net (code "59") (name "unconnected-(U5-D--Pad19)") (class "Default")
      (node (ref "U5") (pin "19") (pinfunction "D-_19") (pintype "passive"))
    )
    (net (code "60") (name "unconnected-(U5-RX1+-Pad23)") (class "Default")
      (node (ref "U5") (pin "23") (pinfunction "RX1+_23") (pintype "passive"))
    )
    (net (code "61") (name "unconnected-(U5-RX1--Pad22)") (class "Default")
      (node (ref "U5") (pin "22") (pinfunction "RX1-_22") (pintype "passive"))
    )
    (net (code "62") (name "unconnected-(U5-RX2+-Pad11)") (class "Default")
      (node (ref "U5") (pin "11") (pinfunction "RX2+_11") (pintype "passive"))
    )
    (net (code "63") (name "unconnected-(U5-RX2--Pad10)") (class "Default")
      (node (ref "U5") (pin "10") (pinfunction "RX2-_10") (pintype "passive"))
    )
    (net (code "64") (name "unconnected-(U5-SBU1-Pad8)") (class "Default")
      (node (ref "U5") (pin "8") (pinfunction "SBU1_8") (pintype "passive"))
    )
    (net (code "65") (name "unconnected-(U5-SBU2-Pad20)") (class "Default")
      (node (ref "U5") (pin "20") (pinfunction "SBU2_20") (pintype "passive"))
    )
    (net (code "66") (name "unconnected-(U5-TX1+-Pad2)") (class "Default")
      (node (ref "U5") (pin "2") (pinfunction "TX1+_2") (pintype "passive"))
    )
    (net (code "67") (name "unconnected-(U5-TX1--Pad3)") (class "Default")
      (node (ref "U5") (pin "3") (pinfunction "TX1-_3") (pintype "passive"))
    )
    (net (code "68") (name "unconnected-(U5-TX2+-Pad14)") (class "Default")
      (node (ref "U5") (pin "14") (pinfunction "TX2+_14") (pintype "passive"))
    )
    (net (code "69") (name "unconnected-(U5-TX2--Pad15)") (class "Default")
      (node (ref "U5") (pin "15") (pinfunction "TX2-_15") (pintype "passive"))
    )
  )
)
